# Rauchmelder_v3_9_0RC2.net
KiCad netlist of a schematic drawn in EAGLE
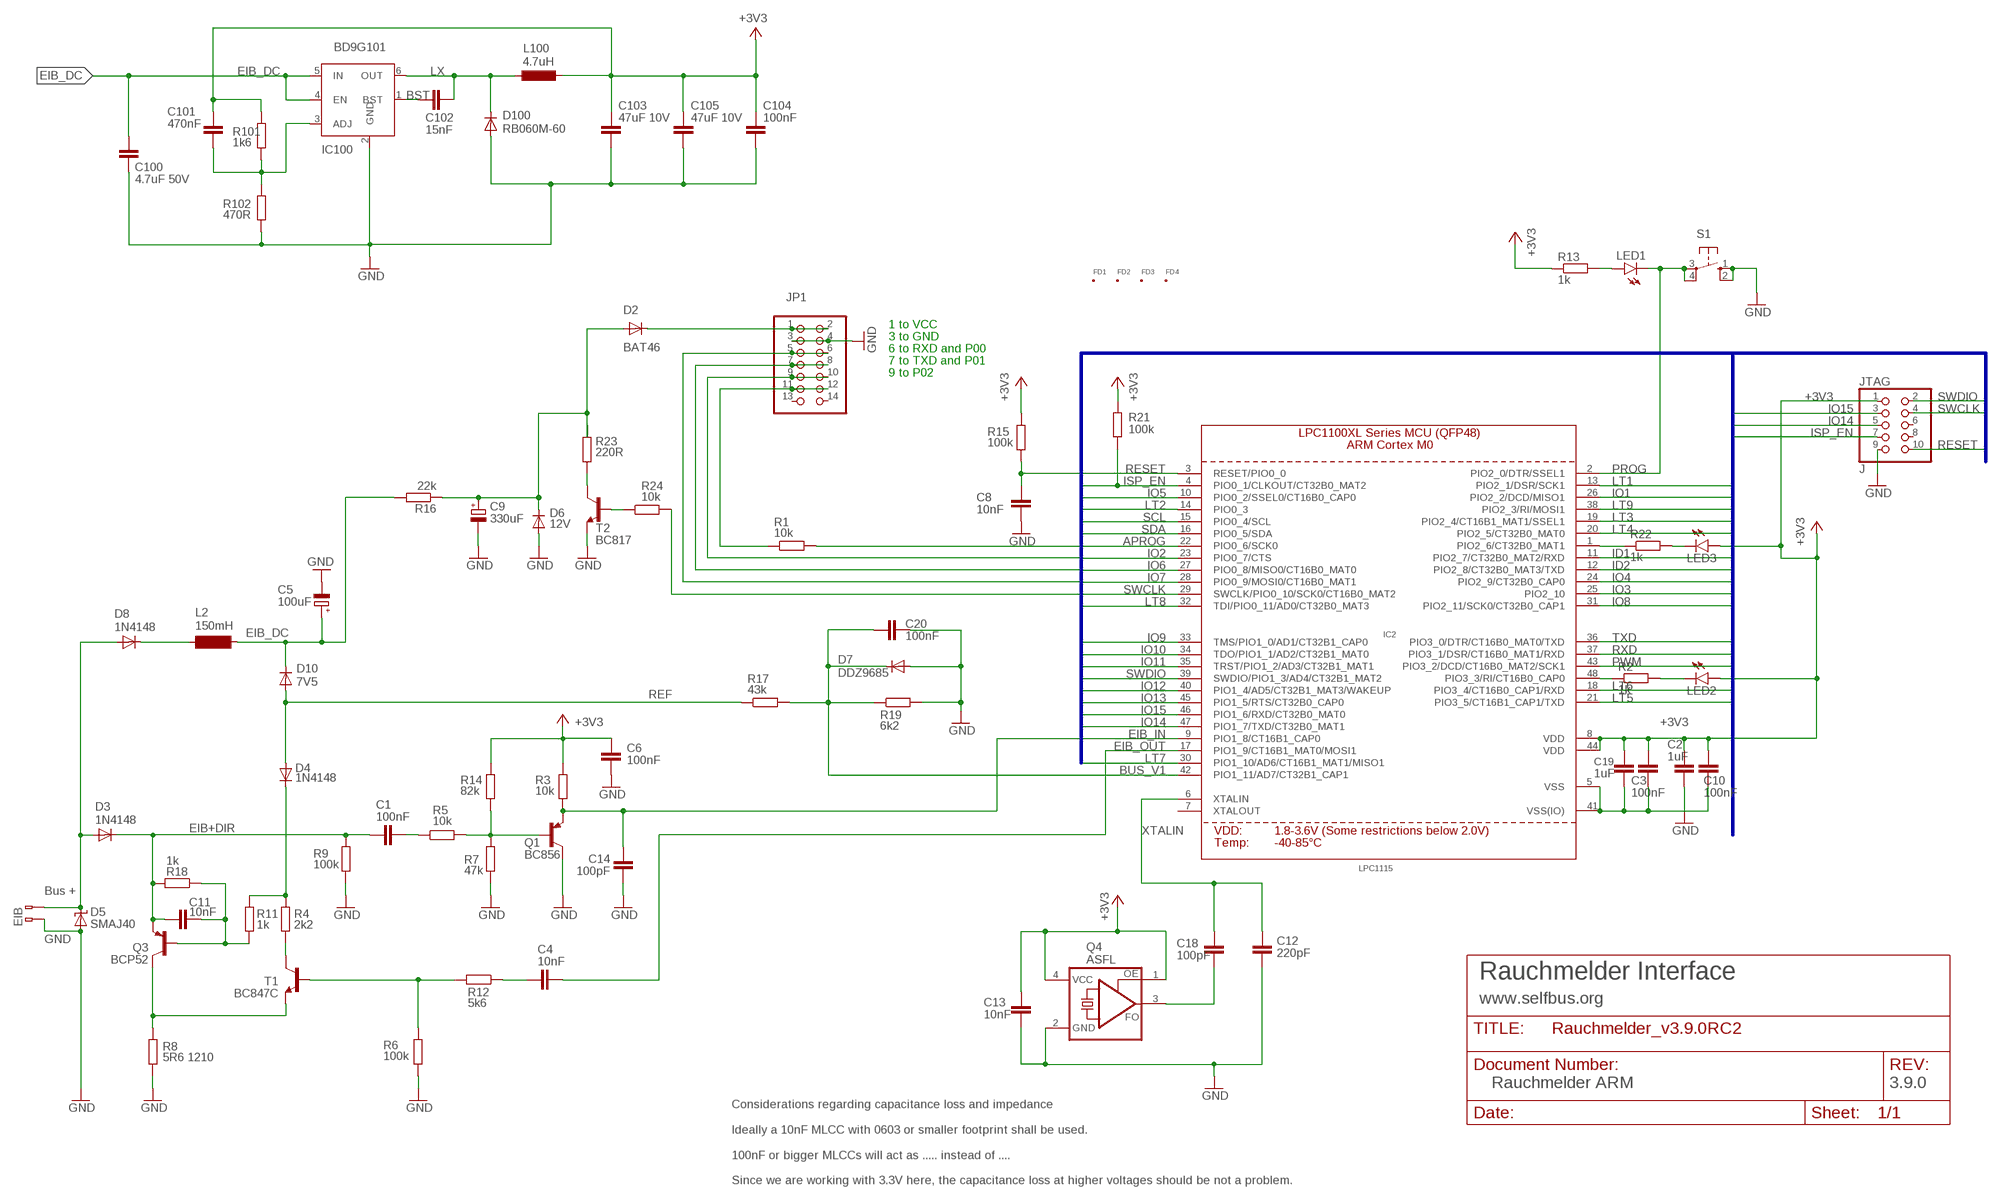
[diagram p0: schematic, sheet 1]

(export (version "E")
  (design (tool "Eeschema 10.0.6"))
  (components
    (comp (ref "C1")
      (value "100nF")
      (footprint "eagle-import:C0805")
      (libsource (lib "eagle-import") (part "C-EUC0805"))
    )
    (comp (ref "C2")
      (value "1uF")
      (footprint "eagle-import:C0805")
      (libsource (lib "eagle-import") (part "C-EUC0805"))
    )
    (comp (ref "C3")
      (value "100nF")
      (footprint "eagle-import:C0805")
      (libsource (lib "eagle-import") (part "C-EUC0805"))
    )
    (comp (ref "C4")
      (value "10nF")
      (footprint "eagle-import:C0805")
      (libsource (lib "eagle-import") (part "C-EUC0805"))
    )
    (comp (ref "C5")
      (value "100uF")
      (footprint "eagle-import:SANYO-OSCON_SMD_C6")
      (libsource (lib "eagle-import") (part "CPOL-EUSANYO_SMD_C6"))
    )
    (comp (ref "C6")
      (value "100nF")
      (footprint "eagle-import:C0805")
      (libsource (lib "eagle-import") (part "C-EUC0805"))
    )
    (comp (ref "C8")
      (value "10nF")
      (footprint "eagle-import:C0805")
      (libsource (lib "eagle-import") (part "C-EUC0805"))
    )
    (comp (ref "C9")
      (value "330uF")
      (footprint "eagle-import:E3,5-8")
      (libsource (lib "eagle-import") (part "CPOL-EUE3.5-8"))
    )
    (comp (ref "C10")
      (value "100nF")
      (footprint "eagle-import:C0805")
      (libsource (lib "eagle-import") (part "C-EUC0805"))
    )
    (comp (ref "C11")
      (value "10nF")
      (footprint "eagle-import:C0805")
      (libsource (lib "eagle-import") (part "C-EUC0805"))
    )
    (comp (ref "C12")
      (value "220pF")
      (footprint "eagle-import:C0805")
      (libsource (lib "eagle-import") (part "C-EUC0805"))
    )
    (comp (ref "C13")
      (value "10nF")
      (footprint "eagle-import:C0805")
      (libsource (lib "eagle-import") (part "C-EUC0805"))
    )
    (comp (ref "C14")
      (value "100pF")
      (footprint "eagle-import:C0805")
      (libsource (lib "eagle-import") (part "C-EUC0805"))
    )
    (comp (ref "C18")
      (value "100pF")
      (footprint "eagle-import:C0805")
      (libsource (lib "eagle-import") (part "C-EUC0805"))
    )
    (comp (ref "C19")
      (value "1uF")
      (footprint "eagle-import:C0805")
      (libsource (lib "eagle-import") (part "C-EUC0805"))
    )
    (comp (ref "C20")
      (value "100nF")
      (footprint "eagle-import:C0805")
      (libsource (lib "eagle-import") (part "C-EUC0805"))
    )
    (comp (ref "C100")
      (value "4.7uF 50V")
      (footprint "eagle-import:C0805")
      (libsource (lib "eagle-import") (part "C-EUC0805"))
    )
    (comp (ref "C101")
      (value "470nF")
      (footprint "eagle-import:C0805")
      (libsource (lib "eagle-import") (part "C-EUC0805"))
    )
    (comp (ref "C102")
      (value "15nF")
      (footprint "eagle-import:C0805")
      (libsource (lib "eagle-import") (part "C-EUC0805"))
    )
    (comp (ref "C103")
      (value "47uF 10V")
      (footprint "eagle-import:C0805")
      (libsource (lib "eagle-import") (part "C-EUC0805"))
    )
    (comp (ref "C104")
      (value "100nF")
      (footprint "eagle-import:C0805")
      (libsource (lib "eagle-import") (part "C-EUC0805"))
    )
    (comp (ref "C105")
      (value "47uF 10V")
      (footprint "eagle-import:C0805")
      (libsource (lib "eagle-import") (part "C-EUC0805"))
    )
    (comp (ref "D2")
      (value "BAT46")
      (footprint "eagle-import:SOD-123")
      (libsource (lib "eagle-import") (part "DIODESOD-123"))
    )
    (comp (ref "D3")
      (value "1N4148")
      (footprint "eagle-import:SOD-123")
      (libsource (lib "eagle-import") (part "DIODESOD-123"))
    )
    (comp (ref "D4")
      (value "1N4148")
      (footprint "eagle-import:SOD-123")
      (libsource (lib "eagle-import") (part "DIODESOD-123"))
    )
    (comp (ref "D5")
      (value "SMAJ40")
      (footprint "eagle-import:SMBJ")
      (libsource (lib "eagle-import") (part "SUPPRESSOR-SMBJ"))
    )
    (comp (ref "D6")
      (value "12V")
      (footprint "eagle-import:SOD-123")
      (libsource (lib "eagle-import") (part "DIODESOD-123"))
    )
    (comp (ref "D7")
      (value "DDZ9685")
      (footprint "eagle-import:SOD-123")
      (libsource (lib "eagle-import") (part "DIODESOD-123"))
    )
    (comp (ref "D8")
      (value "1N4148")
      (footprint "eagle-import:SOD-123")
      (libsource (lib "eagle-import") (part "DIODESOD-123"))
    )
    (comp (ref "D10")
      (value "7V5")
      (footprint "eagle-import:SOD-123")
      (libsource (lib "eagle-import") (part "DIODESOD-123"))
    )
    (comp (ref "D100")
      (value "RB060M-60")
      (footprint "eagle-import:SOD-123")
      (libsource (lib "eagle-import") (part "DIODESOD-123"))
    )
    (comp (ref "FD1")
      (value "FID_40MIL")
      (footprint "eagle-import:FID_040")
      (libsource (lib "eagle-import") (part "FID_40MIL"))
    )
    (comp (ref "FD2")
      (value "FID_40MIL")
      (footprint "eagle-import:FID_040")
      (libsource (lib "eagle-import") (part "FID_40MIL"))
    )
    (comp (ref "FD3")
      (value "FID_40MIL")
      (footprint "eagle-import:FID_040")
      (libsource (lib "eagle-import") (part "FID_40MIL"))
    )
    (comp (ref "FD4")
      (value "FID_40MIL")
      (footprint "eagle-import:FID_040")
      (libsource (lib "eagle-import") (part "FID_40MIL"))
    )
    (comp (ref "IC2")
      (value "LPC1115")
      (footprint "eagle-import:LQFP48")
      (libsource (lib "eagle-import") (part "LPC1113/4/5_QFP48_XLSERIES"))
    )
    (comp (ref "IC100")
      (value "BD9G101")
      (footprint "eagle-import:SOT23-6")
      (libsource (lib "eagle-import") (part "BD9G101GBD9G101G-SOT23-6"))
    )
    (comp (ref "JP1")
      (value "PINHD-2X7")
      (footprint "eagle-import:2X07")
      (libsource (lib "eagle-import") (part "PINHD-2X7"))
    )
    (comp (ref "JTAG")
      (value "J")
      (footprint "eagle-import:2X05M")
      (libsource (lib "eagle-import") (part "PINHD-2X05_2.00"))
    )
    (comp (ref "L2")
      (value "150mH")
      (footprint "eagle-import:BS11")
      (libsource (lib "eagle-import") (part "BS11"))
    )
    (comp (ref "L100")
      (value "4.7uH")
      (footprint "eagle-import:L4532P")
      (libsource (lib "eagle-import") (part "L-EUL4532P"))
    )
    (comp (ref "LED1")
      (value "LEDCHIPLED_0805")
      (footprint "eagle-import:CHIPLED_0805")
      (libsource (lib "eagle-import") (part "LEDCHIPLED_0805"))
    )
    (comp (ref "LED2")
      (value "LEDCHIPLED_0805")
      (footprint "eagle-import:CHIPLED_0805")
      (libsource (lib "eagle-import") (part "LEDCHIPLED_0805"))
    )
    (comp (ref "LED3")
      (value "LEDCHIPLED_0805")
      (footprint "eagle-import:CHIPLED_0805")
      (libsource (lib "eagle-import") (part "LEDCHIPLED_0805"))
    )
    (comp (ref "Q1")
      (value "BC856")
      (footprint "eagle-import:SOT23-BEC")
      (libsource (lib "eagle-import") (part "BC856SMDALT1"))
    )
    (comp (ref "Q3")
      (value "BCP52")
      (footprint "eagle-import:SOT223")
      (libsource (lib "eagle-import") (part "FZT753SMD"))
    )
    (comp (ref "Q4")
      (value "ASFL")
      (footprint "eagle-import:ASF")
      (fields (field (name "MPN") "ASFLM1-50.000MHZ-C-T"))
      (libsource (lib "eagle-import") (part "ASFL"))
    )
    (comp (ref "R1")
      (value "10k")
      (footprint "eagle-import:R0805")
      (libsource (lib "eagle-import") (part "R-EU_R0805"))
    )
    (comp (ref "R2")
      (value "1k")
      (footprint "eagle-import:R0805")
      (libsource (lib "eagle-import") (part "R-EU_R0805"))
    )
    (comp (ref "R3")
      (value "10k")
      (footprint "eagle-import:R0805")
      (libsource (lib "eagle-import") (part "R-EU_R0805"))
    )
    (comp (ref "R4")
      (value "2k2")
      (footprint "eagle-import:R0805")
      (libsource (lib "eagle-import") (part "R-EU_R0805"))
    )
    (comp (ref "R5")
      (value "10k")
      (footprint "eagle-import:R0805")
      (libsource (lib "eagle-import") (part "R-EU_R0805"))
    )
    (comp (ref "R6")
      (value "100k")
      (footprint "eagle-import:R0805")
      (libsource (lib "eagle-import") (part "R-EU_R0805"))
    )
    (comp (ref "R7")
      (value "47k")
      (footprint "eagle-import:R0805")
      (libsource (lib "eagle-import") (part "R-EU_R0805"))
    )
    (comp (ref "R8")
      (value "5R6 1210")
      (footprint "eagle-import:R1210")
      (libsource (lib "eagle-import") (part "R-EU_R1210"))
    )
    (comp (ref "R9")
      (value "100k")
      (footprint "eagle-import:R0805")
      (libsource (lib "eagle-import") (part "R-EU_R0805"))
    )
    (comp (ref "R11")
      (value "1k")
      (footprint "eagle-import:R0805")
      (libsource (lib "eagle-import") (part "R-EU_R0805"))
    )
    (comp (ref "R12")
      (value "5k6")
      (footprint "eagle-import:R0805")
      (libsource (lib "eagle-import") (part "R-EU_R0805"))
    )
    (comp (ref "R13")
      (value "1k")
      (footprint "eagle-import:R0805")
      (libsource (lib "eagle-import") (part "R-EU_R0805"))
    )
    (comp (ref "R14")
      (value "82k")
      (footprint "eagle-import:R0805")
      (libsource (lib "eagle-import") (part "R-EU_R0805"))
    )
    (comp (ref "R15")
      (value "100k")
      (footprint "eagle-import:R0805")
      (libsource (lib "eagle-import") (part "R-EU_R0805"))
    )
    (comp (ref "R16")
      (value "22k")
      (footprint "eagle-import:R0805")
      (libsource (lib "eagle-import") (part "R-EU_R0805"))
    )
    (comp (ref "R17")
      (value "43k")
      (footprint "eagle-import:R0805")
      (libsource (lib "eagle-import") (part "R-EU_R0805"))
    )
    (comp (ref "R18")
      (value "1k")
      (footprint "eagle-import:R0805")
      (libsource (lib "eagle-import") (part "R-EU_R0805"))
    )
    (comp (ref "R19")
      (value "6k2")
      (footprint "eagle-import:R0805")
      (libsource (lib "eagle-import") (part "R-EU_R0805"))
    )
    (comp (ref "R21")
      (value "100k")
      (footprint "eagle-import:R0805")
      (libsource (lib "eagle-import") (part "R-EU_R0805"))
    )
    (comp (ref "R22")
      (value "1k")
      (footprint "eagle-import:R0805")
      (libsource (lib "eagle-import") (part "R-EU_R0805"))
    )
    (comp (ref "R23")
      (value "220R")
      (footprint "eagle-import:R2512")
      (libsource (lib "eagle-import") (part "R-EU_R2512"))
    )
    (comp (ref "R24")
      (value "10k")
      (footprint "eagle-import:R0805")
      (libsource (lib "eagle-import") (part "R-EU_R0805"))
    )
    (comp (ref "R101")
      (value "1k6")
      (footprint "eagle-import:R0805")
      (libsource (lib "eagle-import") (part "R-EU_R0805"))
    )
    (comp (ref "R102")
      (value "470R")
      (footprint "eagle-import:R0805")
      (libsource (lib "eagle-import") (part "R-EU_R0805"))
    )
    (comp (ref "S1")
      (value "10-XX")
      (footprint "eagle-import:B3F-10XX")
      (libsource (lib "eagle-import") (part "10-XX"))
    )
    (comp (ref "T1")
      (value "BC847C")
      (footprint "eagle-import:SOT23")
      (libsource (lib "eagle-import") (part "BC847C"))
    )
    (comp (ref "T2")
      (value "BC817")
      (footprint "eagle-import:SOT23-WIDE")
      (libsource (lib "eagle-import") (part "TRANSISTOR_NPNWIDE"))
    )
    (comp (ref "U$1")
      (value "EIB")
      (footprint "eagle-import:BUSKLEMME243-724")
      (libsource (lib "eagle-import") (part "EIB"))
    )
  )
  (nets
    (net (code "1") (name "+3V3") (class "Default")
      (node (ref "C10") (pin "2") (pinfunction "2_2") (pintype "passive"))
      (node (ref "C101") (pin "2") (pinfunction "2_2") (pintype "passive"))
      (node (ref "C103") (pin "1") (pinfunction "1_1") (pintype "passive"))
      (node (ref "C104") (pin "1") (pinfunction "1_1") (pintype "passive"))
      (node (ref "C105") (pin "1") (pinfunction "1_1") (pintype "passive"))
      (node (ref "C13") (pin "2") (pinfunction "2_2") (pintype "passive"))
      (node (ref "C19") (pin "2") (pinfunction "2_2") (pintype "passive"))
      (node (ref "C2") (pin "2") (pinfunction "2_2") (pintype "passive"))
      (node (ref "C3") (pin "2") (pinfunction "2_2") (pintype "passive"))
      (node (ref "C6") (pin "2") (pinfunction "2_2") (pintype "passive"))
      (node (ref "IC2") (pin "44") (pinfunction "VDD_44") (pintype "power_in"))
      (node (ref "IC2") (pin "8") (pinfunction "VDD_8") (pintype "power_in"))
      (node (ref "JTAG") (pin "1") (pinfunction "1_1") (pintype "passive"))
      (node (ref "L100") (pin "2") (pinfunction "2_2") (pintype "passive"))
      (node (ref "LED2") (pin "A") (pinfunction "A_A") (pintype "passive"))
      (node (ref "LED3") (pin "A") (pinfunction "A_A") (pintype "passive"))
      (node (ref "Q4") (pin "1") (pinfunction "OE_1") (pintype "input"))
      (node (ref "Q4") (pin "4") (pinfunction "VCC_4") (pintype "power_in"))
      (node (ref "R101") (pin "2") (pinfunction "2_2") (pintype "passive"))
      (node (ref "R13") (pin "1") (pinfunction "1_1") (pintype "passive"))
      (node (ref "R14") (pin "2") (pinfunction "2_2") (pintype "passive"))
      (node (ref "R15") (pin "1") (pinfunction "1_1") (pintype "passive"))
      (node (ref "R21") (pin "2") (pinfunction "2_2") (pintype "passive"))
      (node (ref "R3") (pin "2") (pinfunction "2_2") (pintype "passive"))
    )
    (net (code "2") (name "/APROG") (class "Default")
      (node (ref "IC2") (pin "22") (pinfunction "PIO0_6/SCK0_22") (pintype "bidirectional"))
    )
    (net (code "3") (name "/BST") (class "Default")
      (node (ref "C102") (pin "2") (pinfunction "2_2") (pintype "passive"))
      (node (ref "IC100") (pin "1") (pinfunction "BST_1") (pintype "output"))
    )
    (net (code "4") (name "/BUS_V1") (class "Default")
      (node (ref "C20") (pin "2") (pinfunction "2_2") (pintype "passive"))
      (node (ref "D7") (pin "C") (pinfunction "C_C") (pintype "passive"))
      (node (ref "IC2") (pin "42") (pinfunction "PIO1_11/AD7/CT32B1_CAP1_42") (pintype "bidirectional"))
      (node (ref "R17") (pin "2") (pinfunction "2_2") (pintype "passive"))
      (node (ref "R19") (pin "1") (pinfunction "1_1") (pintype "passive"))
    )
    (net (code "5") (name "/EIB+DIR") (class "Default")
      (node (ref "C1") (pin "1") (pinfunction "1_1") (pintype "passive"))
      (node (ref "C11") (pin "1") (pinfunction "1_1") (pintype "passive"))
      (node (ref "D3") (pin "C") (pinfunction "C_C") (pintype "passive"))
      (node (ref "Q3") (pin "3") (pinfunction "E_3") (pintype "passive"))
      (node (ref "R18") (pin "2") (pinfunction "2_2") (pintype "passive"))
      (node (ref "R9") (pin "2") (pinfunction "2_2") (pintype "passive"))
    )
    (net (code "6") (name "/EIB_IN") (class "Default")
      (node (ref "C14") (pin "2") (pinfunction "2_2") (pintype "passive"))
      (node (ref "IC2") (pin "9") (pinfunction "PIO1_8/CT16B1_CAP0_9") (pintype "bidirectional"))
      (node (ref "Q1") (pin "E") (pinfunction "E_E") (pintype "passive"))
      (node (ref "R3") (pin "1") (pinfunction "1_1") (pintype "passive"))
    )
    (net (code "7") (name "/EIB_OUT") (class "Default")
      (node (ref "C4") (pin "2") (pinfunction "2_2") (pintype "passive"))
      (node (ref "IC2") (pin "17") (pinfunction "PIO1_9/CT16B1_MAT0/MOSI1_17") (pintype "bidirectional"))
    )
    (net (code "8") (name "/ID1") (class "Default")
      (node (ref "IC2") (pin "11") (pinfunction "PIO2_7/CT32B0_MAT2/RXD_11") (pintype "bidirectional"))
    )
    (net (code "9") (name "/ID2") (class "Default")
      (node (ref "IC2") (pin "12") (pinfunction "PIO2_8/CT32B0_MAT3/TXD_12") (pintype "bidirectional"))
    )
    (net (code "10") (name "/IO1") (class "Default")
      (node (ref "IC2") (pin "26") (pinfunction "PIO2_2/DCD/MISO1_26") (pintype "bidirectional"))
    )
    (net (code "11") (name "/IO2") (class "Default")
      (node (ref "IC2") (pin "23") (pinfunction "PIO0_7/CTS_23") (pintype "bidirectional"))
    )
    (net (code "12") (name "/IO3") (class "Default")
      (node (ref "IC2") (pin "25") (pinfunction "PIO2_10_25") (pintype "bidirectional"))
    )
    (net (code "13") (name "/IO4") (class "Default")
      (node (ref "IC2") (pin "24") (pinfunction "PIO2_9/CT32B0_CAP0_24") (pintype "bidirectional"))
    )
    (net (code "14") (name "/IO5") (class "Default")
      (node (ref "IC2") (pin "10") (pinfunction "PIO0_2/SSEL0/CT16B0_CAP0_10") (pintype "bidirectional"))
    )
    (net (code "15") (name "/IO6") (class "Default")
      (node (ref "IC2") (pin "27") (pinfunction "PIO0_8/MISO0/CT16B0_MAT0_27") (pintype "bidirectional"))
    )
    (net (code "16") (name "/IO7") (class "Default")
      (node (ref "IC2") (pin "28") (pinfunction "PIO0_9/MOSI0/CT16B0_MAT1_28") (pintype "bidirectional"))
    )
    (net (code "17") (name "/IO8") (class "Default")
      (node (ref "IC2") (pin "31") (pinfunction "PIO2_11/SCK0/CT32B0_CAP1_31") (pintype "bidirectional"))
    )
    (net (code "18") (name "/IO9") (class "Default")
      (node (ref "IC2") (pin "33") (pinfunction "TMS/PIO1_0/AD1/CT32B1_CAP0_33") (pintype "bidirectional"))
    )
    (net (code "19") (name "/IO10") (class "Default")
      (node (ref "IC2") (pin "34") (pinfunction "TDO/PIO1_1/AD2/CT32B1_MAT0_34") (pintype "bidirectional"))
    )
    (net (code "20") (name "/IO11") (class "Default")
      (node (ref "IC2") (pin "35") (pinfunction "TRST/PIO1_2/AD3/CT32B1_MAT1_35") (pintype "bidirectional"))
    )
    (net (code "21") (name "/IO12") (class "Default")
      (node (ref "IC2") (pin "40") (pinfunction "PIO1_4/AD5/CT32B1_MAT3/WAKEUP_40") (pintype "bidirectional"))
    )
    (net (code "22") (name "/IO13") (class "Default")
      (node (ref "IC2") (pin "45") (pinfunction "PIO1_5/RTS/CT32B0_CAP0_45") (pintype "bidirectional"))
    )
    (net (code "23") (name "/IO14") (class "Default")
      (node (ref "IC2") (pin "47") (pinfunction "PIO1_7/TXD/CT32B0_MAT1_47") (pintype "bidirectional"))
      (node (ref "JTAG") (pin "5") (pinfunction "5_5") (pintype "passive"))
    )
    (net (code "24") (name "/IO15") (class "Default")
      (node (ref "IC2") (pin "46") (pinfunction "PIO1_6/RXD/CT32B0_MAT0_46") (pintype "bidirectional"))
      (node (ref "JTAG") (pin "3") (pinfunction "3_3") (pintype "passive"))
    )
    (net (code "25") (name "/ISP_EN") (class "Default")
      (node (ref "IC2") (pin "4") (pinfunction "PIO0_1/CLKOUT/CT32B0_MAT2_4") (pintype "bidirectional"))
      (node (ref "JTAG") (pin "7") (pinfunction "7_7") (pintype "passive"))
      (node (ref "R21") (pin "1") (pinfunction "1_1") (pintype "passive"))
    )
    (net (code "26") (name "/LT1") (class "Default")
      (node (ref "IC2") (pin "13") (pinfunction "PIO2_1/DSR/SCK1_13") (pintype "bidirectional"))
      (node (ref "R24") (pin "2") (pinfunction "2_2") (pintype "passive"))
    )
    (net (code "27") (name "/LT2") (class "Default")
      (node (ref "IC2") (pin "14") (pinfunction "PIO0_3_14") (pintype "bidirectional"))
    )
    (net (code "28") (name "/LT3") (class "Default")
      (node (ref "IC2") (pin "19") (pinfunction "PIO2_4/CT16B1_MAT1/SSEL1_19") (pintype "bidirectional"))
    )
    (net (code "29") (name "/LT4") (class "Default")
      (node (ref "IC2") (pin "20") (pinfunction "PIO2_5/CT32B0_MAT0_20") (pintype "bidirectional"))
    )
    (net (code "30") (name "/LT5") (class "Default")
      (node (ref "IC2") (pin "21") (pinfunction "PIO3_5/CT16B1_CAP1/TXD_21") (pintype "bidirectional"))
      (node (ref "JP1") (pin "10") (pinfunction "10_10") (pintype "passive"))
      (node (ref "JP1") (pin "9") (pinfunction "9_9") (pintype "passive"))
    )
    (net (code "31") (name "/LT6") (class "Default")
      (node (ref "IC2") (pin "18") (pinfunction "PIO3_4/CT16B0_CAP1/RXD_18") (pintype "bidirectional"))
    )
    (net (code "32") (name "/LT7") (class "Default")
      (node (ref "IC2") (pin "30") (pinfunction "PIO1_10/AD6/CT16B1_MAT1/MISO1_30") (pintype "bidirectional"))
    )
    (net (code "33") (name "/LT8") (class "Default")
      (node (ref "IC2") (pin "32") (pinfunction "TDI/PIO0_11/AD0/CT32B0_MAT3_32") (pintype "bidirectional"))
      (node (ref "R1") (pin "2") (pinfunction "2_2") (pintype "passive"))
    )
    (net (code "34") (name "/LT9") (class "Default")
      (node (ref "IC2") (pin "38") (pinfunction "PIO2_3/RI/MOSI1_38") (pintype "bidirectional"))
    )
    (net (code "35") (name "/LX") (class "Default")
      (node (ref "C102") (pin "1") (pinfunction "1_1") (pintype "passive"))
      (node (ref "D100") (pin "C") (pinfunction "C_C") (pintype "passive"))
      (node (ref "IC100") (pin "6") (pinfunction "OUT_6") (pintype "output"))
      (node (ref "L100") (pin "1") (pinfunction "1_1") (pintype "passive"))
    )
    (net (code "36") (name "/PROG") (class "Default")
      (node (ref "IC2") (pin "2") (pinfunction "PIO2_0/DTR/SSEL1_2") (pintype "bidirectional"))
      (node (ref "LED1") (pin "C") (pinfunction "C_C") (pintype "passive"))
      (node (ref "S1") (pin "3") (pinfunction "P_3") (pintype "passive"))
      (node (ref "S1") (pin "4") (pinfunction "P1_4") (pintype "passive"))
    )
    (net (code "37") (name "/PWM") (class "Default")
      (node (ref "IC2") (pin "43") (pinfunction "PIO3_2/DCD/CT16B0_MAT2/SCK1_43") (pintype "bidirectional"))
    )
    (net (code "38") (name "/REF") (class "Default")
      (node (ref "D10") (pin "A") (pinfunction "A_A") (pintype "passive"))
      (node (ref "D4") (pin "A") (pinfunction "A_A") (pintype "passive"))
      (node (ref "R17") (pin "1") (pinfunction "1_1") (pintype "passive"))
    )
    (net (code "39") (name "/RESET") (class "Default")
      (node (ref "C8") (pin "2") (pinfunction "2_2") (pintype "passive"))
      (node (ref "IC2") (pin "3") (pinfunction "RESET/PIO0_0_3") (pintype "bidirectional"))
      (node (ref "JTAG") (pin "10") (pinfunction "10_10") (pintype "passive"))
      (node (ref "R15") (pin "2") (pinfunction "2_2") (pintype "passive"))
    )
    (net (code "40") (name "/RXD") (class "Default")
      (node (ref "IC2") (pin "37") (pinfunction "PIO3_1/DSR/CT16B0_MAT1/RXD_37") (pintype "bidirectional"))
      (node (ref "JP1") (pin "5") (pinfunction "5_5") (pintype "passive"))
      (node (ref "JP1") (pin "6") (pinfunction "6_6") (pintype "passive"))
    )
    (net (code "41") (name "/SCL") (class "Default")
      (node (ref "IC2") (pin "15") (pinfunction "PIO0_4/SCL_15") (pintype "bidirectional"))
    )
    (net (code "42") (name "/SDA") (class "Default")
      (node (ref "IC2") (pin "16") (pinfunction "PIO0_5/SDA_16") (pintype "bidirectional"))
    )
    (net (code "43") (name "/SWCLK") (class "Default")
      (node (ref "IC2") (pin "29") (pinfunction "SWCLK/PIO0_10/SCK0/CT16B0_MAT2_29") (pintype "bidirectional"))
      (node (ref "JTAG") (pin "4") (pinfunction "4_4") (pintype "passive"))
    )
    (net (code "44") (name "/SWDIO") (class "Default")
      (node (ref "IC2") (pin "39") (pinfunction "SWDIO/PIO1_3/AD4/CT32B1_MAT2_39") (pintype "bidirectional"))
      (node (ref "JTAG") (pin "2") (pinfunction "2_2") (pintype "passive"))
    )
    (net (code "45") (name "/TXD") (class "Default")
      (node (ref "IC2") (pin "36") (pinfunction "PIO3_0/DTR/CT16B0_MAT0/TXD_36") (pintype "bidirectional"))
      (node (ref "JP1") (pin "7") (pinfunction "7_7") (pintype "passive"))
      (node (ref "JP1") (pin "8") (pinfunction "8_8") (pintype "passive"))
    )
    (net (code "46") (name "/XTALIN") (class "Default")
      (node (ref "C12") (pin "2") (pinfunction "2_2") (pintype "passive"))
      (node (ref "C18") (pin "2") (pinfunction "2_2") (pintype "passive"))
      (node (ref "IC2") (pin "6") (pinfunction "XTALIN_6") (pintype "input"))
    )
    (net (code "47") (name "EIB_DC") (class "Default")
      (node (ref "C100") (pin "2") (pinfunction "2_2") (pintype "passive"))
      (node (ref "C5") (pin "+") (pinfunction "+_+") (pintype "passive"))
      (node (ref "D10") (pin "C") (pinfunction "C_C") (pintype "passive"))
      (node (ref "IC100") (pin "4") (pinfunction "EN_4") (pintype "input"))
      (node (ref "IC100") (pin "5") (pinfunction "IN_5") (pintype "input"))
      (node (ref "L2") (pin "2") (pinfunction "2_2") (pintype "passive"))
      (node (ref "R16") (pin "2") (pinfunction "2_2") (pintype "passive"))
    )
    (net (code "48") (name "GND") (class "Default")
      (node (ref "C10") (pin "1") (pinfunction "1_1") (pintype "passive"))
      (node (ref "C100") (pin "1") (pinfunction "1_1") (pintype "passive"))
      (node (ref "C103") (pin "2") (pinfunction "2_2") (pintype "passive"))
      (node (ref "C104") (pin "2") (pinfunction "2_2") (pintype "passive"))
      (node (ref "C105") (pin "2") (pinfunction "2_2") (pintype "passive"))
      (node (ref "C12") (pin "1") (pinfunction "1_1") (pintype "passive"))
      (node (ref "C13") (pin "1") (pinfunction "1_1") (pintype "passive"))
      (node (ref "C14") (pin "1") (pinfunction "1_1") (pintype "passive"))
      (node (ref "C19") (pin "1") (pinfunction "1_1") (pintype "passive"))
      (node (ref "C2") (pin "1") (pinfunction "1_1") (pintype "passive"))
      (node (ref "C20") (pin "1") (pinfunction "1_1") (pintype "passive"))
      (node (ref "C3") (pin "1") (pinfunction "1_1") (pintype "passive"))
      (node (ref "C5") (pin "-") (pinfunction "-_-") (pintype "passive"))
      (node (ref "C6") (pin "1") (pinfunction "1_1") (pintype "passive"))
      (node (ref "C8") (pin "1") (pinfunction "1_1") (pintype "passive"))
      (node (ref "C9") (pin "-") (pinfunction "-_-") (pintype "passive"))
      (node (ref "D100") (pin "A") (pinfunction "A_A") (pintype "passive"))
      (node (ref "D5") (pin "A") (pinfunction "A_A") (pintype "passive"))
      (node (ref "D6") (pin "A") (pinfunction "A_A") (pintype "passive"))
      (node (ref "D7") (pin "A") (pinfunction "A_A") (pintype "passive"))
      (node (ref "IC100") (pin "2") (pinfunction "GND_2") (pintype "power_in"))
      (node (ref "IC2") (pin "41") (pinfunction "VSS(IO)_41") (pintype "power_in"))
      (node (ref "IC2") (pin "5") (pinfunction "VSS_5") (pintype "power_in"))
      (node (ref "JP1") (pin "3") (pinfunction "3_3") (pintype "passive"))
      (node (ref "JP1") (pin "4") (pinfunction "4_4") (pintype "passive"))
      (node (ref "JTAG") (pin "9") (pinfunction "9_9") (pintype "passive"))
      (node (ref "Q1") (pin "C") (pinfunction "C_C") (pintype "passive"))
      (node (ref "Q4") (pin "2") (pinfunction "GND_2") (pintype "power_in"))
      (node (ref "R102") (pin "1") (pinfunction "1_1") (pintype "passive"))
      (node (ref "R19") (pin "2") (pinfunction "2_2") (pintype "passive"))
      (node (ref "R6") (pin "1") (pinfunction "1_1") (pintype "passive"))
      (node (ref "R7") (pin "1") (pinfunction "1_1") (pintype "passive"))
      (node (ref "R8") (pin "1") (pinfunction "1_1") (pintype "passive"))
      (node (ref "R9") (pin "1") (pinfunction "1_1") (pintype "passive"))
      (node (ref "S1") (pin "1") (pinfunction "S_1") (pintype "passive"))
      (node (ref "S1") (pin "2") (pinfunction "S1_2") (pintype "passive"))
      (node (ref "T2") (pin "2") (pinfunction "E_2") (pintype "passive"))
      (node (ref "U$1") (pin "1") (pinfunction "B-1_1") (pintype "passive"))
    )
    (net (code "49") (name "Net-(C1-Pad2)") (class "Default")
      (node (ref "C1") (pin "2") (pinfunction "2_2") (pintype "passive"))
      (node (ref "R5") (pin "1") (pinfunction "1_1") (pintype "passive"))
    )
    (net (code "50") (name "Net-(C4-Pad1)") (class "Default")
      (node (ref "C4") (pin "1") (pinfunction "1_1") (pintype "passive"))
      (node (ref "R12") (pin "1") (pinfunction "1_1") (pintype "passive"))
    )
    (net (code "51") (name "Net-(C9-Pad+)") (class "Default")
      (node (ref "C9") (pin "+") (pinfunction "+_+") (pintype "passive"))
      (node (ref "D2") (pin "A") (pinfunction "A_A") (pintype "passive"))
      (node (ref "D6") (pin "C") (pinfunction "C_C") (pintype "passive"))
      (node (ref "R16") (pin "1") (pinfunction "1_1") (pintype "passive"))
      (node (ref "R23") (pin "1") (pinfunction "1_1") (pintype "passive"))
    )
    (net (code "52") (name "Net-(D2-PadC)") (class "Default")
      (node (ref "D2") (pin "C") (pinfunction "C_C") (pintype "passive"))
      (node (ref "JP1") (pin "1") (pinfunction "1_1") (pintype "passive"))
      (node (ref "JP1") (pin "2") (pinfunction "2_2") (pintype "passive"))
    )
    (net (code "53") (name "Net-(D4-PadC)") (class "Default")
      (node (ref "D4") (pin "C") (pinfunction "C_C") (pintype "passive"))
      (node (ref "R11") (pin "2") (pinfunction "2_2") (pintype "passive"))
      (node (ref "R4") (pin "2") (pinfunction "2_2") (pintype "passive"))
    )
    (net (code "54") (name "Net-(D8-PadC)") (class "Default")
      (node (ref "D8") (pin "C") (pinfunction "C_C") (pintype "passive"))
      (node (ref "L2") (pin "1") (pinfunction "1_1") (pintype "passive"))
    )
    (net (code "55") (name "Net-(IC2-PIO2_6{slash}CT32B0_MAT1)") (class "Default")
      (node (ref "IC2") (pin "1") (pinfunction "PIO2_6/CT32B0_MAT1_1") (pintype "bidirectional"))
      (node (ref "R22") (pin "1") (pinfunction "1_1") (pintype "passive"))
    )
    (net (code "56") (name "Net-(IC2-PIO3_3{slash}RI{slash}CT16B0_CAP0)") (class "Default")
      (node (ref "IC2") (pin "48") (pinfunction "PIO3_3/RI/CT16B0_CAP0_48") (pintype "bidirectional"))
      (node (ref "R2") (pin "1") (pinfunction "1_1") (pintype "passive"))
    )
    (net (code "57") (name "Net-(IC100-ADJ)") (class "Default")
      (node (ref "C101") (pin "1") (pinfunction "1_1") (pintype "passive"))
      (node (ref "IC100") (pin "3") (pinfunction "ADJ_3") (pintype "passive"))
      (node (ref "R101") (pin "1") (pinfunction "1_1") (pintype "passive"))
      (node (ref "R102") (pin "2") (pinfunction "2_2") (pintype "passive"))
    )
    (net (code "58") (name "Net-(JP1-Pad11)") (class "Default")
      (node (ref "JP1") (pin "11") (pinfunction "11_11") (pintype "passive"))
      (node (ref "JP1") (pin "12") (pinfunction "12_12") (pintype "passive"))
      (node (ref "R1") (pin "1") (pinfunction "1_1") (pintype "passive"))
    )
    (net (code "59") (name "Net-(LED1-PadA)") (class "Default")
      (node (ref "LED1") (pin "A") (pinfunction "A_A") (pintype "passive"))
      (node (ref "R13") (pin "2") (pinfunction "2_2") (pintype "passive"))
    )
    (net (code "60") (name "Net-(LED2-PadC)") (class "Default")
      (node (ref "LED2") (pin "C") (pinfunction "C_C") (pintype "passive"))
      (node (ref "R2") (pin "2") (pinfunction "2_2") (pintype "passive"))
    )
    (net (code "61") (name "Net-(LED3-PadC)") (class "Default")
      (node (ref "LED3") (pin "C") (pinfunction "C_C") (pintype "passive"))
      (node (ref "R22") (pin "2") (pinfunction "2_2") (pintype "passive"))
    )
    (net (code "62") (name "Net-(Q1-PadB)") (class "Default")
      (node (ref "Q1") (pin "B") (pinfunction "B_B") (pintype "passive"))
      (node (ref "R14") (pin "1") (pinfunction "1_1") (pintype "passive"))
      (node (ref "R5") (pin "2") (pinfunction "2_2") (pintype "passive"))
      (node (ref "R7") (pin "2") (pinfunction "2_2") (pintype "passive"))
    )
    (net (code "63") (name "Net-(Q3-B)") (class "Default")
      (node (ref "C11") (pin "2") (pinfunction "2_2") (pintype "passive"))
      (node (ref "Q3") (pin "1") (pinfunction "B_1") (pintype "passive"))
      (node (ref "R11") (pin "1") (pinfunction "1_1") (pintype "passive"))
      (node (ref "R18") (pin "1") (pinfunction "1_1") (pintype "passive"))
    )
    (net (code "64") (name "Net-(Q4-FO)") (class "Default")
      (node (ref "C18") (pin "1") (pinfunction "1_1") (pintype "passive"))
      (node (ref "Q4") (pin "3") (pinfunction "FO_3") (pintype "output"))
    )
    (net (code "65") (name "Net-(T1-B)") (class "Default")
      (node (ref "R12") (pin "2") (pinfunction "2_2") (pintype "passive"))
      (node (ref "R6") (pin "2") (pinfunction "2_2") (pintype "passive"))
      (node (ref "T1") (pin "1") (pinfunction "B_1") (pintype "passive"))
    )
    (net (code "66") (name "Net-(T1-C)") (class "Default")
      (node (ref "R4") (pin "1") (pinfunction "1_1") (pintype "passive"))
      (node (ref "T1") (pin "3") (pinfunction "C_3") (pintype "passive"))
    )
    (net (code "67") (name "Net-(T1-E)") (class "Default")
      (node (ref "Q3") (pin "2") (pinfunction "C_2") (pintype "passive"))
      (node (ref "Q3") (pin "4") (pinfunction "C_4") (pintype "passive"))
      (node (ref "R8") (pin "2") (pinfunction "2_2") (pintype "passive"))
      (node (ref "T1") (pin "2") (pinfunction "E_2") (pintype "passive"))
    )
    (net (code "68") (name "Net-(T2-B)") (class "Default")
      (node (ref "R24") (pin "1") (pinfunction "1_1") (pintype "passive"))
      (node (ref "T2") (pin "1") (pinfunction "B_1") (pintype "passive"))
    )
    (net (code "69") (name "Net-(T2-C)") (class "Default")
      (node (ref "R23") (pin "2") (pinfunction "2_2") (pintype "passive"))
      (node (ref "T2") (pin "3") (pinfunction "C_3") (pintype "passive"))
    )
    (net (code "70") (name "Net-(U$1-B-2)") (class "Default")
      (node (ref "D3") (pin "A") (pinfunction "A_A") (pintype "passive"))
      (node (ref "D5") (pin "C") (pinfunction "C_C") (pintype "passive"))
      (node (ref "D8") (pin "A") (pinfunction "A_A") (pintype "passive"))
      (node (ref "U$1") (pin "2") (pinfunction "B-2_2") (pintype "passive"))
    )
    (net (code "71") (name "unconnected-(IC2-XTALOUT-Pad7)") (class "Default")
      (node (ref "IC2") (pin "7") (pinfunction "XTALOUT_7") (pintype "output"))
    )
    (net (code "72") (name "unconnected-(JP1-Pad13)") (class "Default")
      (node (ref "JP1") (pin "13") (pinfunction "13_13") (pintype "passive"))
    )
    (net (code "73") (name "unconnected-(JP1-Pad14)") (class "Default")
      (node (ref "JP1") (pin "14") (pinfunction "14_14") (pintype "passive"))
    )
    (net (code "74") (name "unconnected-(JTAG-Pad6)") (class "Default")
      (node (ref "JTAG") (pin "6") (pinfunction "6_6") (pintype "passive"))
    )
    (net (code "75") (name "unconnected-(JTAG-Pad8)") (class "Default")
      (node (ref "JTAG") (pin "8") (pinfunction "8_8") (pintype "passive"))
    )
  )
)
